# m-analog-v0_1.net
KiCad netlist of a schematic drawn in EAGLE
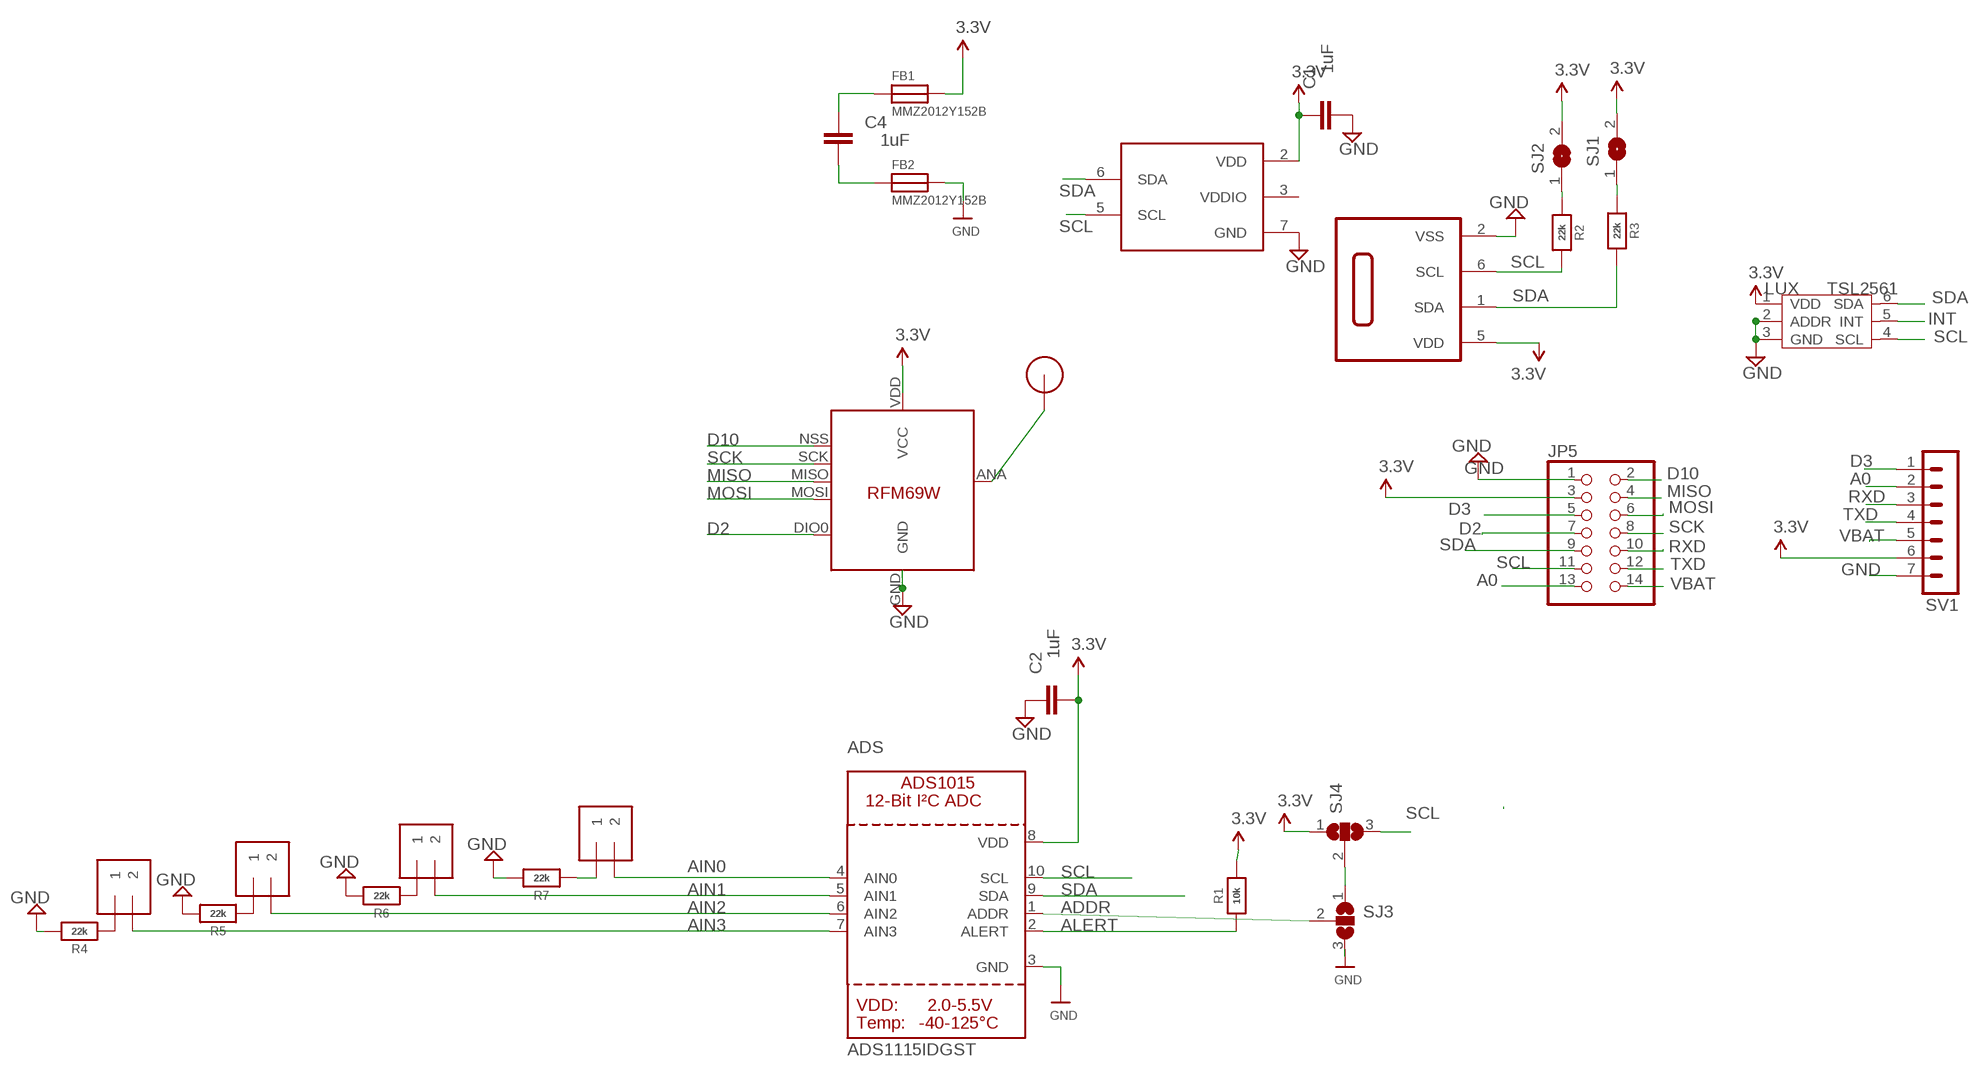
[diagram p0: schematic, sheet 1]

(export (version "E")
  (design (tool "Eeschema 10.0.6"))
  (components
    (comp (ref "ADS")
      (value "ADS1115IDGST")
      (footprint "eagle-import:MSOP10")
      (libsource (lib "eagle-import") (part "ADC_ADS1015"))
    )
    (comp (ref "C1")
      (value "1uF")
      (footprint "eagle-import:0603-CAP")
      (libsource (lib "eagle-import") (part "CAP0603-CAP"))
    )
    (comp (ref "C2")
      (value "1uF")
      (footprint "eagle-import:0603-CAP")
      (libsource (lib "eagle-import") (part "CAP0603-CAP"))
    )
    (comp (ref "C4")
      (value "1uF")
      (footprint "eagle-import:0603-CAP")
      (libsource (lib "eagle-import") (part "CAP0603-CAP"))
    )
    (comp (ref "FB1")
      (value "MMZ2012Y152B")
      (footprint "eagle-import:0805")
      (libsource (lib "eagle-import") (part "FERRITE0805"))
    )
    (comp (ref "FB2")
      (value "MMZ2012Y152B")
      (footprint "eagle-import:0805")
      (libsource (lib "eagle-import") (part "FERRITE0805"))
    )
    (comp (ref "IN0")
      (value "1X2-3.5MM")
      (footprint "eagle-import:1X2-3.5MM")
      (libsource (lib "eagle-import") (part "1X2-3.5MM"))
    )
    (comp (ref "IN1")
      (value "1X2-3.5MM")
      (footprint "eagle-import:1X2-3.5MM")
      (libsource (lib "eagle-import") (part "1X2-3.5MM"))
    )
    (comp (ref "IN2")
      (value "1X2-3.5MM")
      (footprint "eagle-import:1X2-3.5MM")
      (libsource (lib "eagle-import") (part "1X2-3.5MM"))
    )
    (comp (ref "IN3")
      (value "1X2-3.5MM")
      (footprint "eagle-import:1X2-3.5MM")
      (libsource (lib "eagle-import") (part "1X2-3.5MM"))
    )
    (comp (ref "JP5")
      (value "PINHD-2X7")
      (footprint "eagle-import:2X07")
      (libsource (lib "eagle-import") (part "PINHD-2X7"))
    )
    (comp (ref "LUX")
      (value "TSL2561")
      (footprint "eagle-import:TMB-6")
      (libsource (lib "eagle-import") (part "TSL2561T"))
    )
    (comp (ref "R1")
      (value "10k")
      (footprint "eagle-import:0603-NO")
      (libsource (lib "eagle-import") (part "RESISTOR_0603_NOOUT"))
    )
    (comp (ref "R2")
      (value "22k")
      (footprint "eagle-import:0603-NO")
      (libsource (lib "eagle-import") (part "RESISTOR_0603_NOOUT"))
    )
    (comp (ref "R3")
      (value "22k")
      (footprint "eagle-import:0603-NO")
      (libsource (lib "eagle-import") (part "RESISTOR_0603_NOOUT"))
    )
    (comp (ref "R4")
      (value "22k")
      (footprint "eagle-import:0603-NO")
      (libsource (lib "eagle-import") (part "RESISTOR_0603_NOOUT"))
    )
    (comp (ref "R5")
      (value "22k")
      (footprint "eagle-import:0603-NO")
      (libsource (lib "eagle-import") (part "RESISTOR_0603_NOOUT"))
    )
    (comp (ref "R6")
      (value "22k")
      (footprint "eagle-import:0603-NO")
      (libsource (lib "eagle-import") (part "RESISTOR_0603_NOOUT"))
    )
    (comp (ref "R7")
      (value "22k")
      (footprint "eagle-import:0603-NO")
      (libsource (lib "eagle-import") (part "RESISTOR_0603_NOOUT"))
    )
    (comp (ref "SJ1") (value "SJ") (footprint "eagle-import:SJ") (libsource (lib "eagle-import") (part "SJ")))
    (comp (ref "SJ2") (value "SJ") (footprint "eagle-import:SJ") (libsource (lib "eagle-import") (part "SJ")))
    (comp (ref "SJ3")
      (value "SJ2W")
      (footprint "eagle-import:SJ_2")
      (libsource (lib "eagle-import") (part "SJ2W"))
    )
    (comp (ref "SJ4")
      (value "SJ2W")
      (footprint "eagle-import:SJ_2")
      (libsource (lib "eagle-import") (part "SJ2W"))
    )
    (comp (ref "SN1")
      (value "SHT21")
      (footprint "eagle-import:DFN6_SHT")
      (libsource (lib "eagle-import") (part "SHT21"))
    )
    (comp (ref "SV1")
      (value "MA07-1")
      (footprint "eagle-import:MA07-1")
      (libsource (lib "eagle-import") (part "MA07-1"))
    )
    (comp (ref "U$1")
      (value "RFM12B_ANTENNA")
      (footprint "eagle-import:RFM12B-ANTENNA")
      (libsource (lib "eagle-import") (part "RFM12B_ANTENNA"))
    )
    (comp (ref "U$5")
      (value "RFM69")
      (footprint "eagle-import:RFM69W-MINPADS")
      (libsource (lib "eagle-import") (part "RFM69"))
    )
    (comp (ref "U1")
      (value "BMP180")
      (footprint "eagle-import:BMP180")
      (libsource (lib "eagle-import") (part "BMP180"))
    )
  )
  (nets
    (net (code "1") (name "/A0") (class "Default")
      (node (ref "JP5") (pin "13") (pinfunction "13_13") (pintype "passive"))
      (node (ref "SV1") (pin "2") (pinfunction "2_2") (pintype "passive"))
    )
    (net (code "2") (name "/ADDR") (class "Default")
      (node (ref "ADS") (pin "1") (pinfunction "ADDR_1") (pintype "bidirectional"))
      (node (ref "SJ3") (pin "2") (pinfunction "2_2") (pintype "passive"))
    )
    (net (code "3") (name "/AIN0") (class "Default")
      (node (ref "ADS") (pin "4") (pinfunction "AIN0_4") (pintype "bidirectional"))
      (node (ref "IN0") (pin "2") (pinfunction "2_2") (pintype "passive"))
    )
    (net (code "4") (name "/AIN1") (class "Default")
      (node (ref "ADS") (pin "5") (pinfunction "AIN1_5") (pintype "bidirectional"))
      (node (ref "IN1") (pin "2") (pinfunction "2_2") (pintype "passive"))
    )
    (net (code "5") (name "/AIN2") (class "Default")
      (node (ref "ADS") (pin "6") (pinfunction "AIN2_6") (pintype "bidirectional"))
      (node (ref "IN2") (pin "2") (pinfunction "2_2") (pintype "passive"))
    )
    (net (code "6") (name "/AIN3") (class "Default")
      (node (ref "ADS") (pin "7") (pinfunction "AIN3_7") (pintype "bidirectional"))
      (node (ref "IN3") (pin "2") (pinfunction "2_2") (pintype "passive"))
    )
    (net (code "7") (name "/ALERT") (class "Default")
      (node (ref "ADS") (pin "2") (pinfunction "ALERT_2") (pintype "bidirectional"))
      (node (ref "R1") (pin "1") (pinfunction "1_1") (pintype "passive"))
    )
    (net (code "8") (name "/D2") (class "Default")
      (node (ref "JP5") (pin "7") (pinfunction "7_7") (pintype "passive"))
      (node (ref "U$5") (pin "DIO0") (pinfunction "DIO0_DIO0") (pintype "open_collector"))
    )
    (net (code "9") (name "/D3") (class "Default")
      (node (ref "JP5") (pin "5") (pinfunction "5_5") (pintype "passive"))
      (node (ref "SV1") (pin "1") (pinfunction "1_1") (pintype "passive"))
    )
    (net (code "10") (name "/D10") (class "Default")
      (node (ref "JP5") (pin "2") (pinfunction "2_2") (pintype "passive"))
      (node (ref "U$5") (pin "NSS") (pinfunction "SEL_NSS") (pintype "input"))
    )
    (net (code "11") (name "/INT") (class "Default")
      (node (ref "LUX") (pin "5") (pinfunction "INT_5") (pintype "output"))
    )
    (net (code "12") (name "/MISO") (class "Default")
      (node (ref "JP5") (pin "4") (pinfunction "4_4") (pintype "passive"))
      (node (ref "U$5") (pin "MISO") (pinfunction "MISO_MISO") (pintype "input"))
    )
    (net (code "13") (name "/MOSI") (class "Default")
      (node (ref "JP5") (pin "6") (pinfunction "6_6") (pintype "passive"))
      (node (ref "U$5") (pin "MOSI") (pinfunction "MOSI_MOSI") (pintype "output"))
    )
    (net (code "14") (name "/RXD") (class "Default")
      (node (ref "JP5") (pin "10") (pinfunction "10_10") (pintype "passive"))
      (node (ref "SV1") (pin "3") (pinfunction "3_3") (pintype "passive"))
    )
    (net (code "15") (name "/SCK") (class "Default")
      (node (ref "JP5") (pin "8") (pinfunction "8_8") (pintype "passive"))
      (node (ref "U$5") (pin "SCK") (pinfunction "SCK_SCK") (pintype "input"))
    )
    (net (code "16") (name "/SCL") (class "Default")
      (node (ref "ADS") (pin "10") (pinfunction "SCL_10") (pintype "bidirectional"))
      (node (ref "JP5") (pin "11") (pinfunction "11_11") (pintype "passive"))
      (node (ref "LUX") (pin "4") (pinfunction "SCL_4") (pintype "input"))
      (node (ref "R2") (pin "2") (pinfunction "2_2") (pintype "passive"))
      (node (ref "SJ4") (pin "3") (pinfunction "3_3") (pintype "passive"))
      (node (ref "SN1") (pin "6") (pinfunction "SCL_6") (pintype "bidirectional"))
      (node (ref "U1") (pin "5") (pinfunction "SCL_5") (pintype "input"))
    )
    (net (code "17") (name "/SDA") (class "Default")
      (node (ref "ADS") (pin "9") (pinfunction "SDA_9") (pintype "bidirectional"))
      (node (ref "JP5") (pin "9") (pinfunction "9_9") (pintype "passive"))
      (node (ref "LUX") (pin "6") (pinfunction "SDA_6") (pintype "bidirectional"))
      (node (ref "R3") (pin "2") (pinfunction "2_2") (pintype "passive"))
      (node (ref "SN1") (pin "1") (pinfunction "SDA_1") (pintype "bidirectional"))
      (node (ref "U1") (pin "6") (pinfunction "SDA_6") (pintype "bidirectional"))
    )
    (net (code "18") (name "/TXD") (class "Default")
      (node (ref "JP5") (pin "12") (pinfunction "12_12") (pintype "passive"))
      (node (ref "SV1") (pin "4") (pinfunction "4_4") (pintype "passive"))
    )
    (net (code "19") (name "/VBAT") (class "Default")
      (node (ref "JP5") (pin "14") (pinfunction "14_14") (pintype "passive"))
      (node (ref "SV1") (pin "5") (pinfunction "5_5") (pintype "passive"))
    )
    (net (code "20") (name "/VDDIO") (class "Default")
      (node (ref "U1") (pin "3") (pinfunction "VDDIO_3") (pintype "power_in"))
    )
    (net (code "21") (name "3.3V") (class "Default")
      (node (ref "ADS") (pin "8") (pinfunction "VDD_8") (pintype "bidirectional"))
      (node (ref "C1") (pin "2") (pinfunction "2_2") (pintype "passive"))
      (node (ref "C2") (pin "1") (pinfunction "1_1") (pintype "passive"))
      (node (ref "FB1") (pin "2") (pinfunction "P$2_2") (pintype "bidirectional"))
      (node (ref "JP5") (pin "3") (pinfunction "3_3") (pintype "passive"))
      (node (ref "LUX") (pin "1") (pinfunction "VDD_1") (pintype "power_in"))
      (node (ref "R1") (pin "2") (pinfunction "2_2") (pintype "passive"))
      (node (ref "SJ1") (pin "2") (pinfunction "2_2") (pintype "passive"))
      (node (ref "SJ2") (pin "2") (pinfunction "2_2") (pintype "passive"))
      (node (ref "SJ4") (pin "1") (pinfunction "1_1") (pintype "passive"))
      (node (ref "SN1") (pin "5") (pinfunction "VDD_5") (pintype "power_in"))
      (node (ref "SV1") (pin "6") (pinfunction "6_6") (pintype "passive"))
      (node (ref "U$5") (pin "VDD") (pinfunction "VCC_VDD") (pintype "power_in"))
      (node (ref "U1") (pin "2") (pinfunction "VDD_2") (pintype "power_in"))
    )
    (net (code "22") (name "GND") (class "Default")
      (node (ref "ADS") (pin "3") (pinfunction "GND_3") (pintype "bidirectional"))
      (node (ref "C1") (pin "1") (pinfunction "1_1") (pintype "passive"))
      (node (ref "C2") (pin "2") (pinfunction "2_2") (pintype "passive"))
      (node (ref "FB2") (pin "2") (pinfunction "P$2_2") (pintype "bidirectional"))
      (node (ref "JP5") (pin "1") (pinfunction "1_1") (pintype "passive"))
      (node (ref "LUX") (pin "2") (pinfunction "ADDR_2") (pintype "input"))
      (node (ref "LUX") (pin "3") (pinfunction "GND_3") (pintype "power_in"))
      (node (ref "R4") (pin "2") (pinfunction "2_2") (pintype "passive"))
      (node (ref "R5") (pin "2") (pinfunction "2_2") (pintype "passive"))
      (node (ref "R6") (pin "2") (pinfunction "2_2") (pintype "passive"))
      (node (ref "R7") (pin "2") (pinfunction "2_2") (pintype "passive"))
      (node (ref "SJ3") (pin "3") (pinfunction "3_3") (pintype "passive"))
      (node (ref "SN1") (pin "2") (pinfunction "VSS_2") (pintype "power_in"))
      (node (ref "SV1") (pin "7") (pinfunction "7_7") (pintype "passive"))
      (node (ref "U$5") (pin "GND") (pinfunction "GND_GND") (pintype "power_in"))
      (node (ref "U1") (pin "7") (pinfunction "GND_7") (pintype "power_in"))
    )
    (net (code "23") (name "Net-(FB1-P$1)") (class "Default")
      (node (ref "C4") (pin "2") (pinfunction "2_2") (pintype "passive"))
      (node (ref "FB1") (pin "1") (pinfunction "P$1_1") (pintype "bidirectional"))
    )
    (net (code "24") (name "Net-(FB2-P$1)") (class "Default")
      (node (ref "C4") (pin "1") (pinfunction "1_1") (pintype "passive"))
      (node (ref "FB2") (pin "1") (pinfunction "P$1_1") (pintype "bidirectional"))
    )
    (net (code "25") (name "Net-(IN0-Pad1)") (class "Default")
      (node (ref "IN0") (pin "1") (pinfunction "1_1") (pintype "passive"))
      (node (ref "R7") (pin "1") (pinfunction "1_1") (pintype "passive"))
    )
    (net (code "26") (name "Net-(IN1-Pad1)") (class "Default")
      (node (ref "IN1") (pin "1") (pinfunction "1_1") (pintype "passive"))
      (node (ref "R6") (pin "1") (pinfunction "1_1") (pintype "passive"))
    )
    (net (code "27") (name "Net-(IN2-Pad1)") (class "Default")
      (node (ref "IN2") (pin "1") (pinfunction "1_1") (pintype "passive"))
      (node (ref "R5") (pin "1") (pinfunction "1_1") (pintype "passive"))
    )
    (net (code "28") (name "Net-(IN3-Pad1)") (class "Default")
      (node (ref "IN3") (pin "1") (pinfunction "1_1") (pintype "passive"))
      (node (ref "R4") (pin "1") (pinfunction "1_1") (pintype "passive"))
    )
    (net (code "29") (name "Net-(R2-Pad1)") (class "Default")
      (node (ref "R2") (pin "1") (pinfunction "1_1") (pintype "passive"))
      (node (ref "SJ2") (pin "1") (pinfunction "1_1") (pintype "passive"))
    )
    (net (code "30") (name "Net-(R3-Pad1)") (class "Default")
      (node (ref "R3") (pin "1") (pinfunction "1_1") (pintype "passive"))
      (node (ref "SJ1") (pin "1") (pinfunction "1_1") (pintype "passive"))
    )
    (net (code "31") (name "Net-(SJ3-Pad1)") (class "Default")
      (node (ref "SJ3") (pin "1") (pinfunction "1_1") (pintype "passive"))
      (node (ref "SJ4") (pin "2") (pinfunction "2_2") (pintype "passive"))
    )
    (net (code "32") (name "Net-(U$1-1)") (class "Default")
      (node (ref "U$1") (pin "P$1") (pinfunction "1_P$1") (pintype "bidirectional"))
      (node (ref "U$5") (pin "ANA") (pinfunction "ANT_ANA") (pintype "passive"))
    )
  )
)
